# Lidar.net
KiCad netlist of a schematic drawn in EAGLE
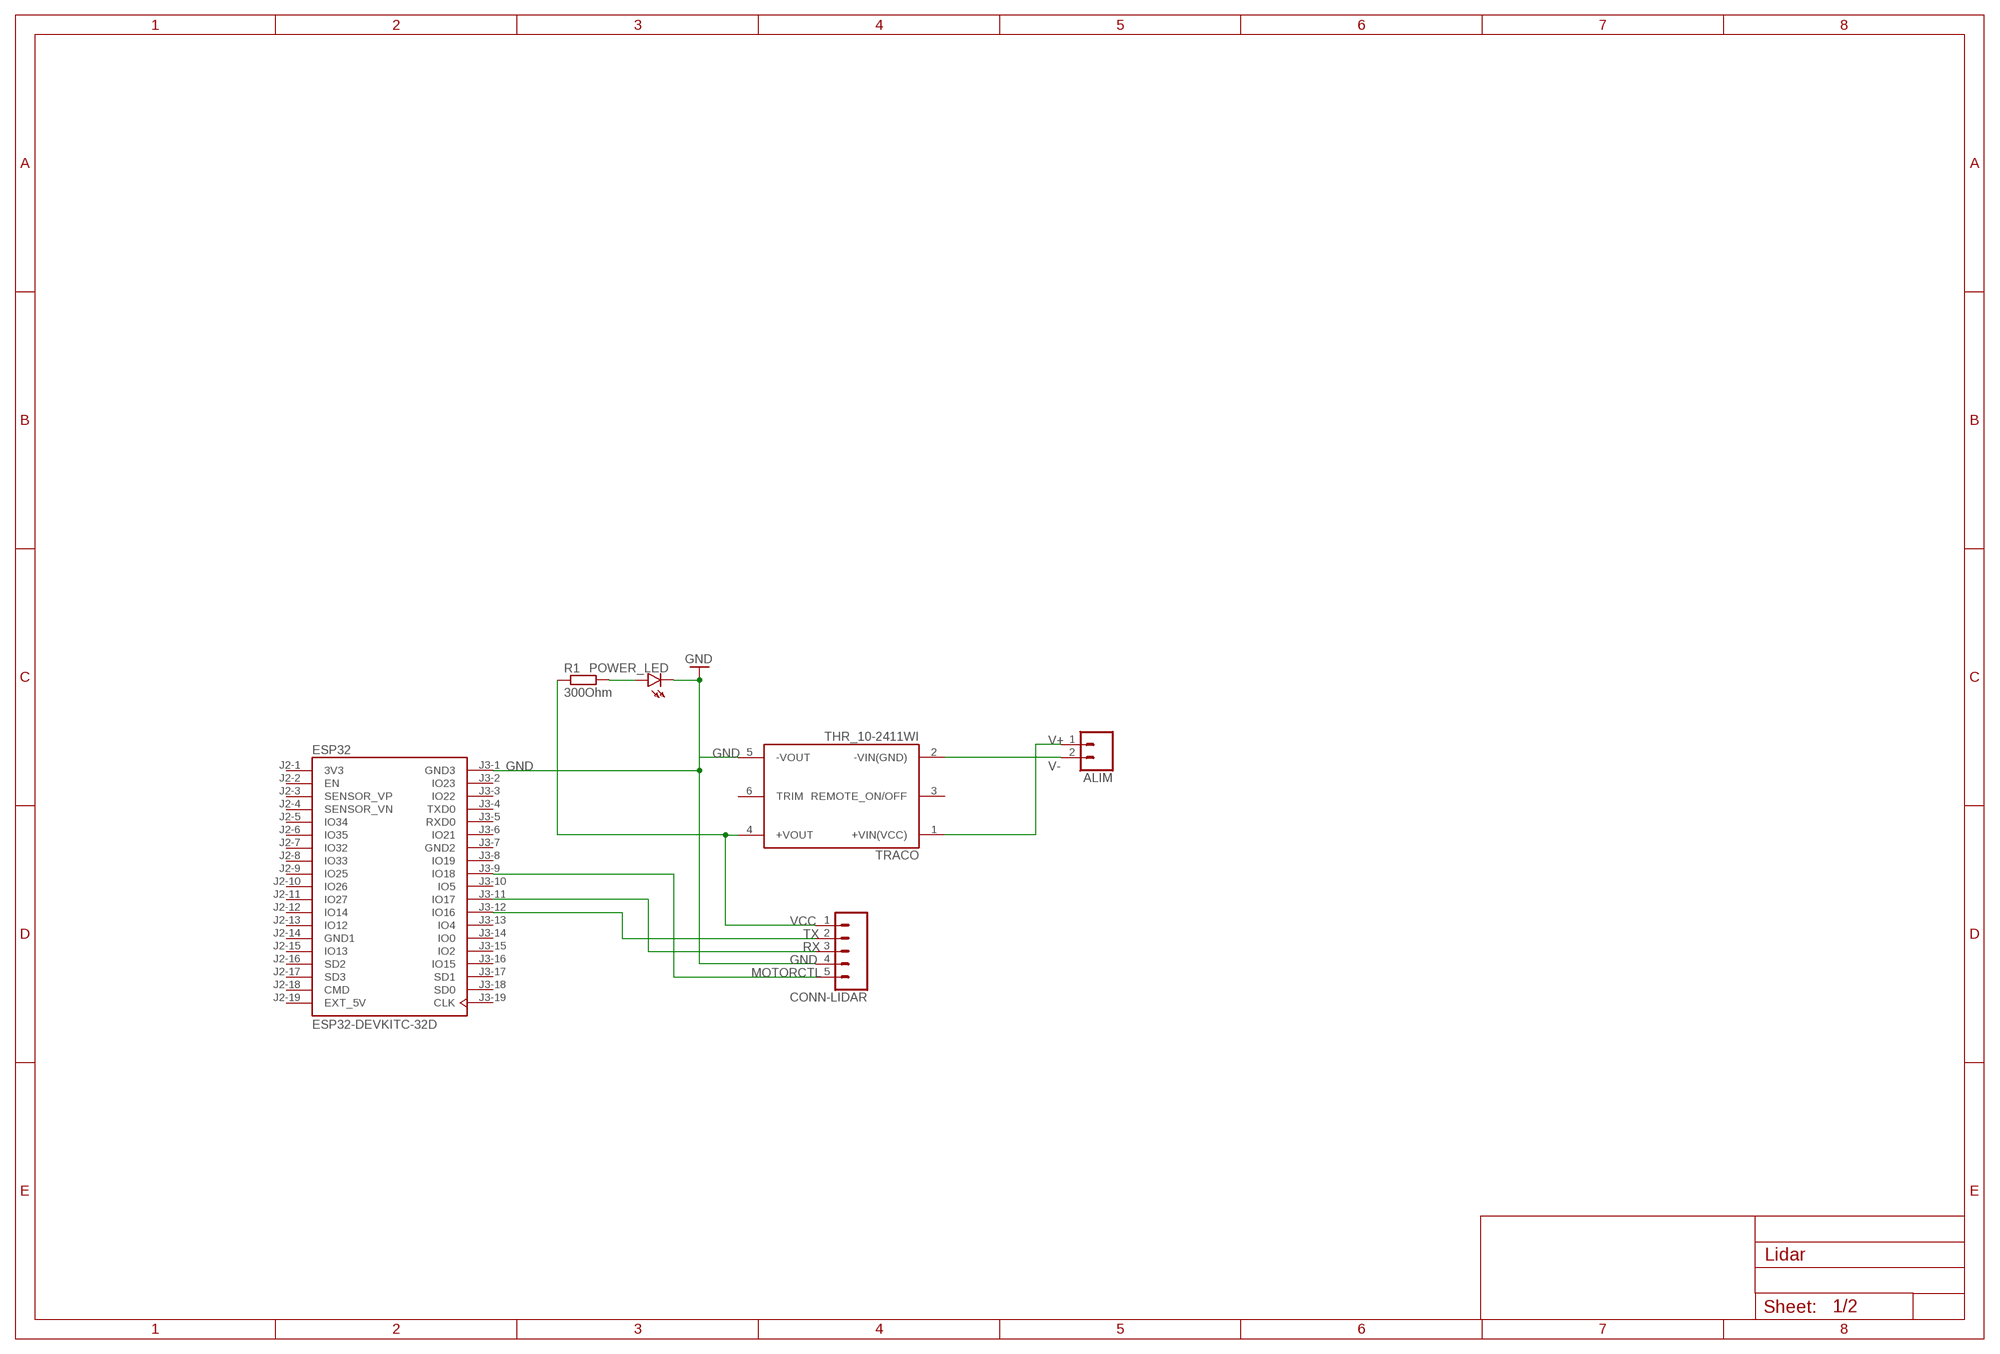
[diagram p0: schematic, sheet 1]

(export (version "E")
  (design (tool "Eeschema 10.0.6"))
  (components
    (comp (ref "ALIM")
      (value "CONN_02POLAR")
      (footprint "eagle-import:MOLEX-1X2")
      (libsource (lib "eagle-import") (part "CONN_02POLAR"))
    )
    (comp (ref "CONN-LIDAR")
      (value "CONN_05PTH")
      (footprint "eagle-import:1X05")
      (libsource (lib "eagle-import") (part "CONN_05PTH"))
    )
    (comp (ref "ESP32")
      (value "ESP32-DEVKITC-32D")
      (footprint "eagle-import:MODULE_ESP32-DEVKITC-32D")
      (fields (field (name "MF") "Espressif Systems"))
      (libsource (lib "eagle-import") (part "ESP32-DEVKITC-32D"))
    )
    (comp (ref "POWER_LED")
      (value "HLMP6")
      (footprint "eagle-import:HLMP6")
      (fields (field (name "MF") "AGILENT TECHNOLOGIES") (field (name "MPN") "HLMP-6500"))
      (libsource (lib "eagle-import") (part "HLMP6"))
    )
    (comp (ref "R1")
      (value "300Ohm")
      (footprint "eagle-import:0411_15")
      (libsource (lib "eagle-import") (part "R-EU_0411/15"))
    )
    (comp (ref "TRACO")
      (value "THR_10-2411WI")
      (footprint "eagle-import:CONV_THR_10-2411WI")
      (fields (field (name "MF") "Traco Power") (field (name "MP") "THR 10-2411WI"))
      (libsource (lib "eagle-import") (part "THR_10-2411WI"))
    )
  )
  (nets
    (net (code "1") (name "3V3") (class "Default")
      (node (ref "ESP32") (pin "J2-1") (pinfunction "3V3_J2-1") (pintype "power_in"))
    )
    (net (code "2") (name "EXT_5V") (class "Default")
      (node (ref "ESP32") (pin "J2-19") (pinfunction "EXT_5V_J2-19") (pintype "power_in"))
    )
    (net (code "3") (name "GND") (class "Default")
      (node (ref "CONN-LIDAR") (pin "4") (pinfunction "4_4") (pintype "passive"))
      (node (ref "ESP32") (pin "J3-1") (pinfunction "GND3_J3-1") (pintype "power_in"))
      (node (ref "POWER_LED") (pin "K") (pinfunction "K_K") (pintype "passive"))
      (node (ref "TRACO") (pin "5") (pinfunction "-VOUT_5") (pintype "output"))
    )
    (net (code "4") (name "GND1") (class "Default")
      (node (ref "ESP32") (pin "J2-14") (pinfunction "GND1_J2-14") (pintype "power_in"))
    )
    (net (code "5") (name "GND2") (class "Default")
      (node (ref "ESP32") (pin "J3-7") (pinfunction "GND2_J3-7") (pintype "power_in"))
    )
    (net (code "6") (name "MOTORCTL") (class "Default")
      (node (ref "CONN-LIDAR") (pin "5") (pinfunction "5_5") (pintype "passive"))
      (node (ref "ESP32") (pin "J3-9") (pinfunction "IO18_J3-9") (pintype "bidirectional"))
    )
    (net (code "7") (name "Net-(POWER_LED-PadA)") (class "Default")
      (node (ref "POWER_LED") (pin "A") (pinfunction "A_A") (pintype "passive"))
      (node (ref "R1") (pin "2") (pinfunction "2_2") (pintype "passive"))
    )
    (net (code "8") (name "RX") (class "Default")
      (node (ref "CONN-LIDAR") (pin "3") (pinfunction "3_3") (pintype "passive"))
      (node (ref "ESP32") (pin "J3-11") (pinfunction "IO17_J3-11") (pintype "bidirectional"))
    )
    (net (code "9") (name "TX") (class "Default")
      (node (ref "CONN-LIDAR") (pin "2") (pinfunction "2_2") (pintype "passive"))
      (node (ref "ESP32") (pin "J3-12") (pinfunction "IO16_J3-12") (pintype "bidirectional"))
    )
    (net (code "10") (name "V+") (class "Default")
      (node (ref "ALIM") (pin "1") (pinfunction "1_1") (pintype "passive"))
      (node (ref "TRACO") (pin "1") (pinfunction "+VIN(VCC)_1") (pintype "input"))
    )
    (net (code "11") (name "V-") (class "Default")
      (node (ref "ALIM") (pin "2") (pinfunction "2_2") (pintype "passive"))
      (node (ref "TRACO") (pin "2") (pinfunction "-VIN(GND)_2") (pintype "input"))
    )
    (net (code "12") (name "VCC") (class "Default")
      (node (ref "CONN-LIDAR") (pin "1") (pinfunction "1_1") (pintype "passive"))
      (node (ref "R1") (pin "1") (pinfunction "1_1") (pintype "passive"))
      (node (ref "TRACO") (pin "4") (pinfunction "+VOUT_4") (pintype "output"))
    )
    (net (code "13") (name "unconnected-(ESP32-CLK-PadJ3-19)") (class "Default")
      (node (ref "ESP32") (pin "J3-19") (pinfunction "CLK_J3-19") (pintype "input"))
    )
    (net (code "14") (name "unconnected-(ESP32-CMD-PadJ2-18)") (class "Default")
      (node (ref "ESP32") (pin "J2-18") (pinfunction "CMD_J2-18") (pintype "bidirectional"))
    )
    (net (code "15") (name "unconnected-(ESP32-EN-PadJ2-2)") (class "Default")
      (node (ref "ESP32") (pin "J2-2") (pinfunction "EN_J2-2") (pintype "input"))
    )
    (net (code "16") (name "unconnected-(ESP32-IO0-PadJ3-14)") (class "Default")
      (node (ref "ESP32") (pin "J3-14") (pinfunction "IO0_J3-14") (pintype "bidirectional"))
    )
    (net (code "17") (name "unconnected-(ESP32-IO2-PadJ3-15)") (class "Default")
      (node (ref "ESP32") (pin "J3-15") (pinfunction "IO2_J3-15") (pintype "bidirectional"))
    )
    (net (code "18") (name "unconnected-(ESP32-IO4-PadJ3-13)") (class "Default")
      (node (ref "ESP32") (pin "J3-13") (pinfunction "IO4_J3-13") (pintype "bidirectional"))
    )
    (net (code "19") (name "unconnected-(ESP32-IO5-PadJ3-10)") (class "Default")
      (node (ref "ESP32") (pin "J3-10") (pinfunction "IO5_J3-10") (pintype "bidirectional"))
    )
    (net (code "20") (name "unconnected-(ESP32-IO12-PadJ2-13)") (class "Default")
      (node (ref "ESP32") (pin "J2-13") (pinfunction "IO12_J2-13") (pintype "bidirectional"))
    )
    (net (code "21") (name "unconnected-(ESP32-IO13-PadJ2-15)") (class "Default")
      (node (ref "ESP32") (pin "J2-15") (pinfunction "IO13_J2-15") (pintype "bidirectional"))
    )
    (net (code "22") (name "unconnected-(ESP32-IO14-PadJ2-12)") (class "Default")
      (node (ref "ESP32") (pin "J2-12") (pinfunction "IO14_J2-12") (pintype "bidirectional"))
    )
    (net (code "23") (name "unconnected-(ESP32-IO15-PadJ3-16)") (class "Default")
      (node (ref "ESP32") (pin "J3-16") (pinfunction "IO15_J3-16") (pintype "bidirectional"))
    )
    (net (code "24") (name "unconnected-(ESP32-IO19-PadJ3-8)") (class "Default")
      (node (ref "ESP32") (pin "J3-8") (pinfunction "IO19_J3-8") (pintype "bidirectional"))
    )
    (net (code "25") (name "unconnected-(ESP32-IO21-PadJ3-6)") (class "Default")
      (node (ref "ESP32") (pin "J3-6") (pinfunction "IO21_J3-6") (pintype "bidirectional"))
    )
    (net (code "26") (name "unconnected-(ESP32-IO22-PadJ3-3)") (class "Default")
      (node (ref "ESP32") (pin "J3-3") (pinfunction "IO22_J3-3") (pintype "bidirectional"))
    )
    (net (code "27") (name "unconnected-(ESP32-IO23-PadJ3-2)") (class "Default")
      (node (ref "ESP32") (pin "J3-2") (pinfunction "IO23_J3-2") (pintype "bidirectional"))
    )
    (net (code "28") (name "unconnected-(ESP32-IO25-PadJ2-9)") (class "Default")
      (node (ref "ESP32") (pin "J2-9") (pinfunction "IO25_J2-9") (pintype "bidirectional"))
    )
    (net (code "29") (name "unconnected-(ESP32-IO26-PadJ2-10)") (class "Default")
      (node (ref "ESP32") (pin "J2-10") (pinfunction "IO26_J2-10") (pintype "bidirectional"))
    )
    (net (code "30") (name "unconnected-(ESP32-IO27-PadJ2-11)") (class "Default")
      (node (ref "ESP32") (pin "J2-11") (pinfunction "IO27_J2-11") (pintype "bidirectional"))
    )
    (net (code "31") (name "unconnected-(ESP32-IO32-PadJ2-7)") (class "Default")
      (node (ref "ESP32") (pin "J2-7") (pinfunction "IO32_J2-7") (pintype "bidirectional"))
    )
    (net (code "32") (name "unconnected-(ESP32-IO33-PadJ2-8)") (class "Default")
      (node (ref "ESP32") (pin "J2-8") (pinfunction "IO33_J2-8") (pintype "bidirectional"))
    )
    (net (code "33") (name "unconnected-(ESP32-IO34-PadJ2-5)") (class "Default")
      (node (ref "ESP32") (pin "J2-5") (pinfunction "IO34_J2-5") (pintype "bidirectional"))
    )
    (net (code "34") (name "unconnected-(ESP32-IO35-PadJ2-6)") (class "Default")
      (node (ref "ESP32") (pin "J2-6") (pinfunction "IO35_J2-6") (pintype "bidirectional"))
    )
    (net (code "35") (name "unconnected-(ESP32-RXD0-PadJ3-5)") (class "Default")
      (node (ref "ESP32") (pin "J3-5") (pinfunction "RXD0_J3-5") (pintype "input"))
    )
    (net (code "36") (name "unconnected-(ESP32-SD0-PadJ3-18)") (class "Default")
      (node (ref "ESP32") (pin "J3-18") (pinfunction "SD0_J3-18") (pintype "bidirectional"))
    )
    (net (code "37") (name "unconnected-(ESP32-SD1-PadJ3-17)") (class "Default")
      (node (ref "ESP32") (pin "J3-17") (pinfunction "SD1_J3-17") (pintype "bidirectional"))
    )
    (net (code "38") (name "unconnected-(ESP32-SD2-PadJ2-16)") (class "Default")
      (node (ref "ESP32") (pin "J2-16") (pinfunction "SD2_J2-16") (pintype "bidirectional"))
    )
    (net (code "39") (name "unconnected-(ESP32-SD3-PadJ2-17)") (class "Default")
      (node (ref "ESP32") (pin "J2-17") (pinfunction "SD3_J2-17") (pintype "bidirectional"))
    )
    (net (code "40") (name "unconnected-(ESP32-SENSOR_VN-PadJ2-4)") (class "Default")
      (node (ref "ESP32") (pin "J2-4") (pinfunction "SENSOR_VN_J2-4") (pintype "input"))
    )
    (net (code "41") (name "unconnected-(ESP32-SENSOR_VP-PadJ2-3)") (class "Default")
      (node (ref "ESP32") (pin "J2-3") (pinfunction "SENSOR_VP_J2-3") (pintype "input"))
    )
    (net (code "42") (name "unconnected-(ESP32-TXD0-PadJ3-4)") (class "Default")
      (node (ref "ESP32") (pin "J3-4") (pinfunction "TXD0_J3-4") (pintype "output"))
    )
    (net (code "43") (name "unconnected-(TRACO-REMOTE_ON{slash}OFF-Pad3)") (class "Default")
      (node (ref "TRACO") (pin "3") (pinfunction "REMOTE_ON/OFF_3") (pintype "input"))
    )
    (net (code "44") (name "unconnected-(TRACO-TRIM-Pad6)") (class "Default")
      (node (ref "TRACO") (pin "6") (pinfunction "TRIM_6") (pintype "passive"))
    )
  )
)
